# Node.net
KiCad netlist of a schematic drawn in EAGLE
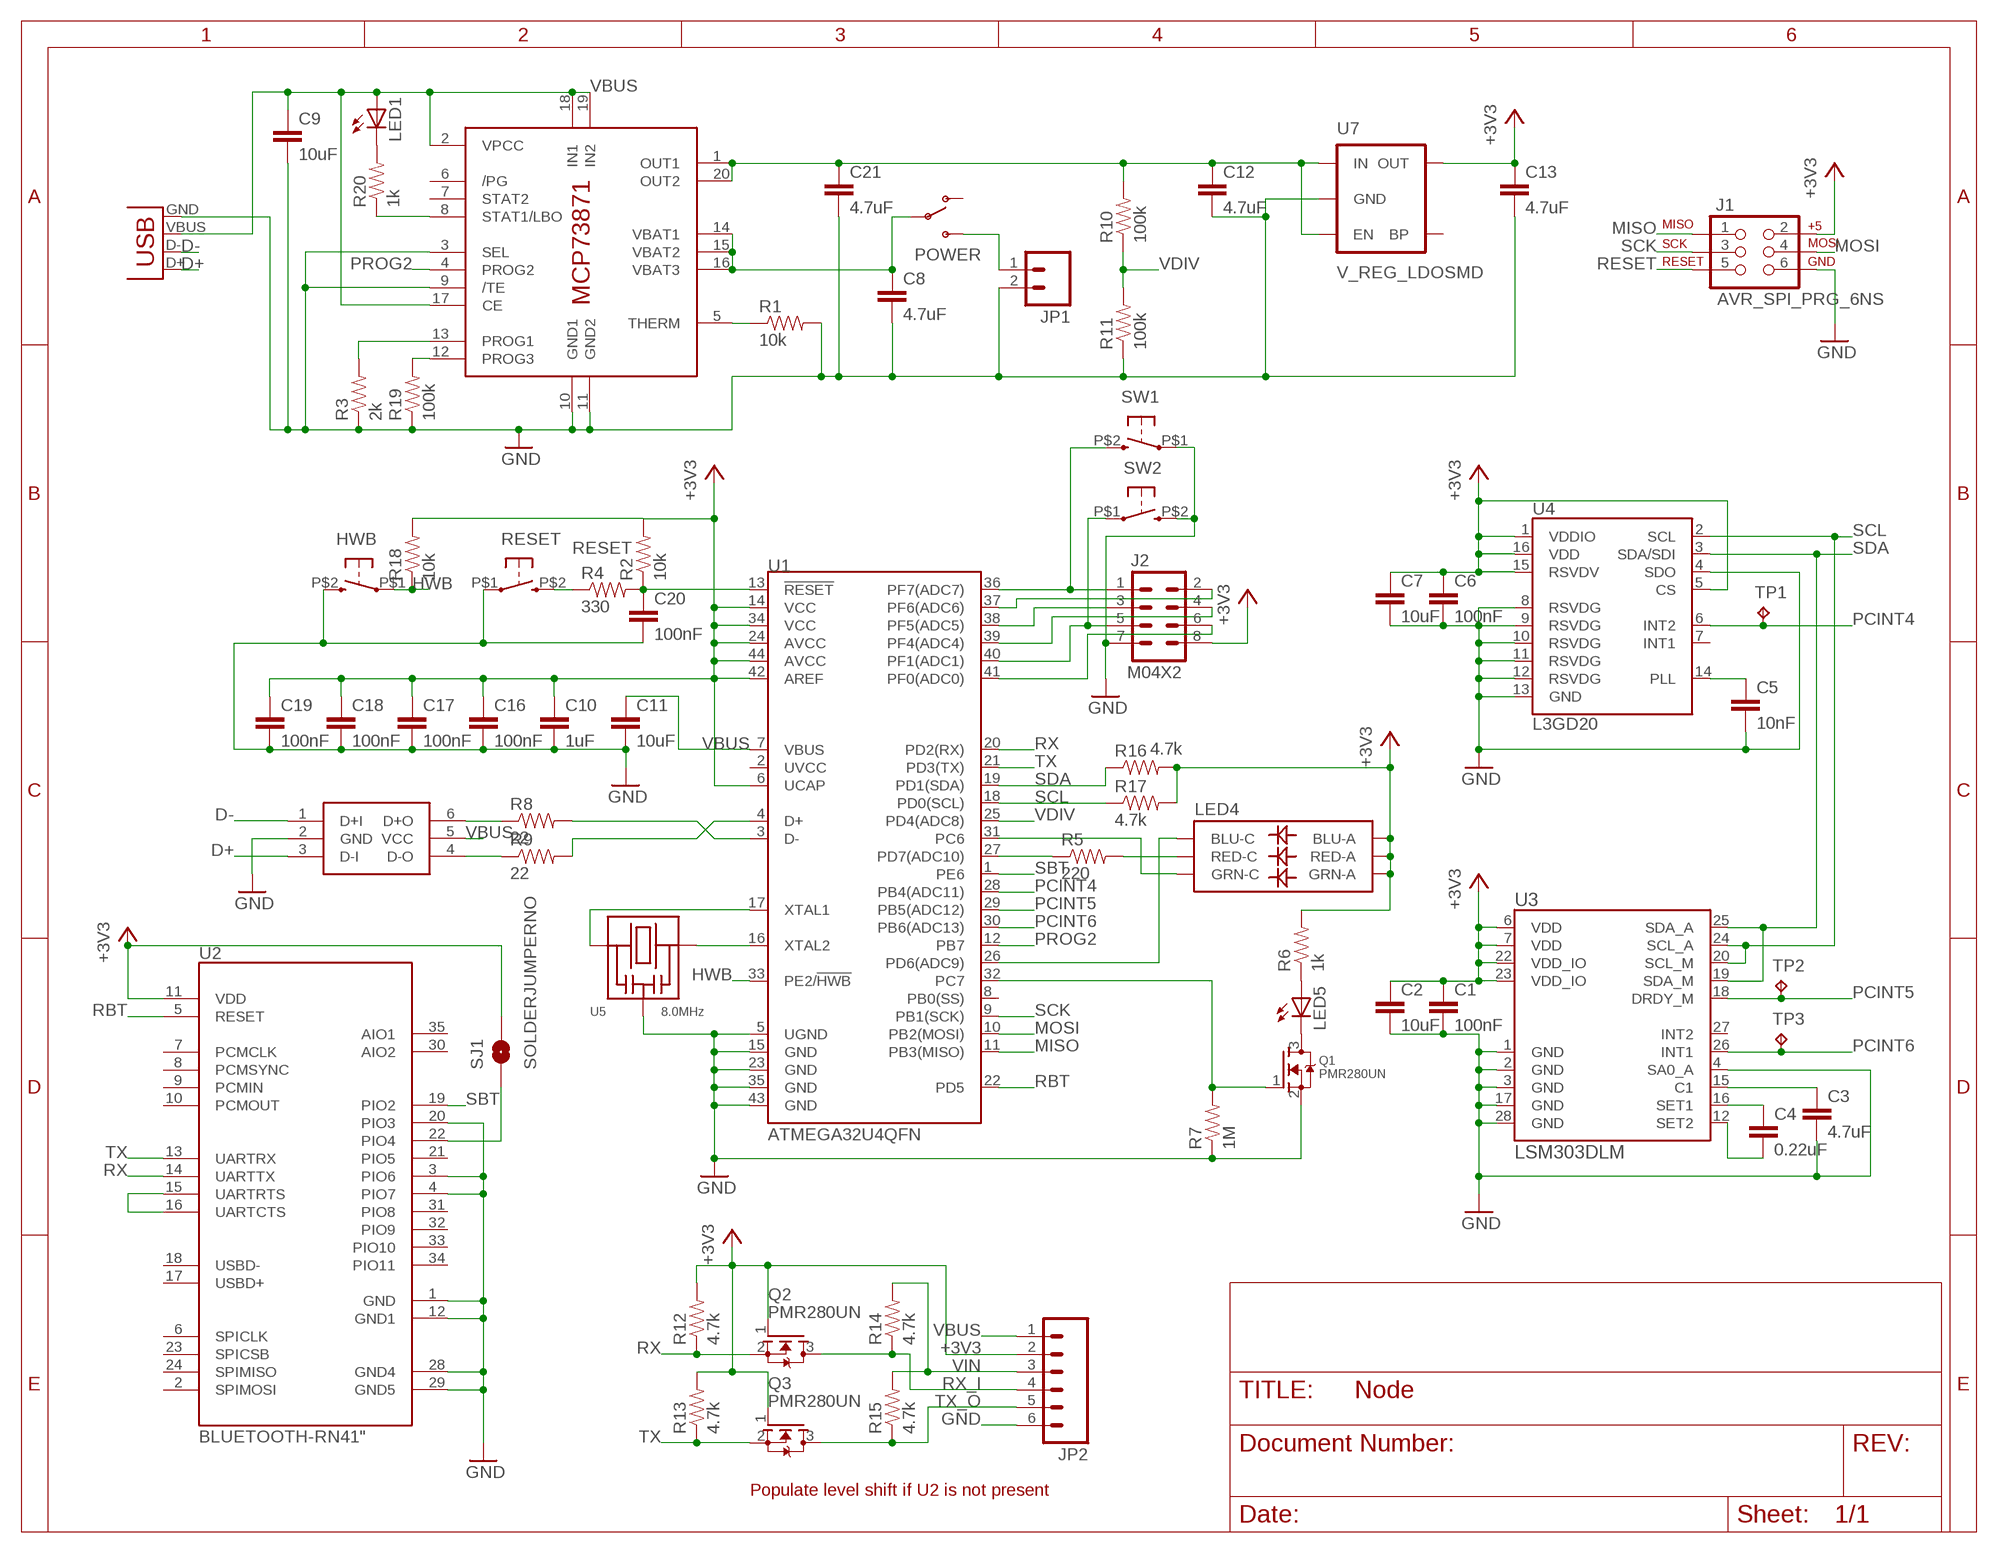
[diagram p0: schematic, sheet 1]

(export (version "E")
  (design (tool "Eeschema 10.0.6"))
  (components
    (comp (ref "C1")
      (value "100nF")
      (footprint "eagle-import:0402-CAP")
      (libsource (lib "eagle-import") (part "CAP0402-CAP"))
    )
    (comp (ref "C2")
      (value "10uF")
      (footprint "eagle-import:0603-CAP")
      (libsource (lib "eagle-import") (part "CAP0603-CAP"))
    )
    (comp (ref "C3")
      (value "4.7uF")
      (footprint "eagle-import:0603-CAP")
      (libsource (lib "eagle-import") (part "CAP0603-CAP"))
    )
    (comp (ref "C4")
      (value "0.22uF")
      (footprint "eagle-import:0402-CAP")
      (libsource (lib "eagle-import") (part "CAP0402-CAP"))
    )
    (comp (ref "C5")
      (value "10nF")
      (footprint "eagle-import:0402-CAP")
      (libsource (lib "eagle-import") (part "CAP0402-CAP"))
    )
    (comp (ref "C6")
      (value "100nF")
      (footprint "eagle-import:0402-CAP")
      (libsource (lib "eagle-import") (part "CAP0402-CAP"))
    )
    (comp (ref "C7")
      (value "10uF")
      (footprint "eagle-import:0603-CAP")
      (libsource (lib "eagle-import") (part "CAP0603-CAP"))
    )
    (comp (ref "C8")
      (value "4.7uF")
      (footprint "eagle-import:0603-CAP")
      (libsource (lib "eagle-import") (part "CAP0603-CAP"))
    )
    (comp (ref "C9")
      (value "10uF")
      (footprint "eagle-import:0603-CAP")
      (libsource (lib "eagle-import") (part "CAP0603-CAP"))
    )
    (comp (ref "C10")
      (value "1uF")
      (footprint "eagle-import:0402-CAP")
      (libsource (lib "eagle-import") (part "CAP0402-CAP"))
    )
    (comp (ref "C11")
      (value "10uF")
      (footprint "eagle-import:0603-CAP")
      (libsource (lib "eagle-import") (part "CAP0603-CAP"))
    )
    (comp (ref "C12")
      (value "4.7uF")
      (footprint "eagle-import:0603-CAP")
      (libsource (lib "eagle-import") (part "CAP0603-CAP"))
    )
    (comp (ref "C13")
      (value "4.7uF")
      (footprint "eagle-import:0603-CAP")
      (libsource (lib "eagle-import") (part "CAP0603-CAP"))
    )
    (comp (ref "C16")
      (value "100nF")
      (footprint "eagle-import:0402-CAP")
      (libsource (lib "eagle-import") (part "CAP0402-CAP"))
    )
    (comp (ref "C17")
      (value "100nF")
      (footprint "eagle-import:0402-CAP")
      (libsource (lib "eagle-import") (part "CAP0402-CAP"))
    )
    (comp (ref "C18")
      (value "100nF")
      (footprint "eagle-import:0402-CAP")
      (libsource (lib "eagle-import") (part "CAP0402-CAP"))
    )
    (comp (ref "C19")
      (value "100nF")
      (footprint "eagle-import:0402-CAP")
      (libsource (lib "eagle-import") (part "CAP0402-CAP"))
    )
    (comp (ref "C20")
      (value "100nF")
      (footprint "eagle-import:0402-CAP")
      (libsource (lib "eagle-import") (part "CAP0402-CAP"))
    )
    (comp (ref "C21")
      (value "4.7uF")
      (footprint "eagle-import:0603-CAP")
      (libsource (lib "eagle-import") (part "CAP0603-CAP"))
    )
    (comp (ref "HWB")
      (value "KSS")
      (footprint "eagle-import:KSS")
      (libsource (lib "eagle-import") (part "KSS"))
    )
    (comp (ref "J1")
      (value "AVR_SPI_PRG_6NS")
      (footprint "eagle-import:2X3-NS")
      (libsource (lib "eagle-import") (part "AVR_SPI_PRG_6NS"))
    )
    (comp (ref "J2")
      (value "M04X2")
      (footprint "eagle-import:2X4")
      (libsource (lib "eagle-import") (part "M04X2"))
    )
    (comp (ref "JP1")
      (value "M02-JST-2MM-SMT")
      (footprint "eagle-import:JST-2-SMD")
      (libsource (lib "eagle-import") (part "M02-JST-2MM-SMT"))
    )
    (comp (ref "JP2")
      (value "M06SIP")
      (footprint "eagle-import:1X06")
      (libsource (lib "eagle-import") (part "M06SIP"))
    )
    (comp (ref "LED1")
      (value "LED0603")
      (footprint "eagle-import:LED-0603")
      (libsource (lib "eagle-import") (part "LED0603"))
    )
    (comp (ref "LED4")
      (value "LED-TRICOLOR-5050LED-TRICOLOR-0606")
      (footprint "eagle-import:0606")
      (libsource (lib "eagle-import") (part "LED-TRICOLOR-5050LED-TRICOLOR-0606"))
    )
    (comp (ref "LED5")
      (value "LED0603")
      (footprint "eagle-import:LED-0603")
      (libsource (lib "eagle-import") (part "LED0603"))
    )
    (comp (ref "POWER")
      (value "SWITCH-SPST-SMD-A")
      (footprint "eagle-import:SWITCH-SPST-SMD-A")
      (libsource (lib "eagle-import") (part "SWITCH-SPST-SMD-A"))
    )
    (comp (ref "Q1")
      (value "PMR280UN")
      (footprint "eagle-import:SOT416")
      (libsource (lib "eagle-import") (part "MOSFET-N"))
    )
    (comp (ref "Q2")
      (value "PMR280UN")
      (footprint "eagle-import:SOT416")
      (libsource (lib "eagle-import") (part "MOSFET-N"))
    )
    (comp (ref "Q3")
      (value "PMR280UN")
      (footprint "eagle-import:SOT416")
      (libsource (lib "eagle-import") (part "MOSFET-N"))
    )
    (comp (ref "R1")
      (value "10k")
      (footprint "eagle-import:0402-RES")
      (libsource (lib "eagle-import") (part "RESISTOR0402-RES"))
    )
    (comp (ref "R2")
      (value "10k")
      (footprint "eagle-import:0402-RES")
      (libsource (lib "eagle-import") (part "RESISTOR0402-RES"))
    )
    (comp (ref "R3")
      (value "2k")
      (footprint "eagle-import:0402-RES")
      (libsource (lib "eagle-import") (part "RESISTOR0402-RES"))
    )
    (comp (ref "R4")
      (value "330")
      (footprint "eagle-import:0402-RES")
      (libsource (lib "eagle-import") (part "RESISTOR0402-RES"))
    )
    (comp (ref "R5")
      (value "220")
      (footprint "eagle-import:0402-RES")
      (libsource (lib "eagle-import") (part "RESISTOR0402-RES"))
    )
    (comp (ref "R6")
      (value "1k")
      (footprint "eagle-import:0402-RES")
      (libsource (lib "eagle-import") (part "RESISTOR0402-RES"))
    )
    (comp (ref "R7")
      (value "1M")
      (footprint "eagle-import:0402-RES")
      (libsource (lib "eagle-import") (part "RESISTOR0402-RES"))
    )
    (comp (ref "R8")
      (value "22")
      (footprint "eagle-import:0402-RES")
      (libsource (lib "eagle-import") (part "RESISTOR0402-RES"))
    )
    (comp (ref "R9")
      (value "22")
      (footprint "eagle-import:0402-RES")
      (libsource (lib "eagle-import") (part "RESISTOR0402-RES"))
    )
    (comp (ref "R10")
      (value "100k")
      (footprint "eagle-import:0402-RES")
      (libsource (lib "eagle-import") (part "RESISTOR0402-RES"))
    )
    (comp (ref "R11")
      (value "100k")
      (footprint "eagle-import:0402-RES")
      (libsource (lib "eagle-import") (part "RESISTOR0402-RES"))
    )
    (comp (ref "R12")
      (value "4.7k")
      (footprint "eagle-import:0402-RES")
      (libsource (lib "eagle-import") (part "RESISTOR0402-RES"))
    )
    (comp (ref "R13")
      (value "4.7k")
      (footprint "eagle-import:0402-RES")
      (libsource (lib "eagle-import") (part "RESISTOR0402-RES"))
    )
    (comp (ref "R14")
      (value "4.7k")
      (footprint "eagle-import:0402-RES")
      (libsource (lib "eagle-import") (part "RESISTOR0402-RES"))
    )
    (comp (ref "R15")
      (value "4.7k")
      (footprint "eagle-import:0402-RES")
      (libsource (lib "eagle-import") (part "RESISTOR0402-RES"))
    )
    (comp (ref "R16")
      (value "4.7k")
      (footprint "eagle-import:0402-RES")
      (libsource (lib "eagle-import") (part "RESISTOR0402-RES"))
    )
    (comp (ref "R17")
      (value "4.7k")
      (footprint "eagle-import:0402-RES")
      (libsource (lib "eagle-import") (part "RESISTOR0402-RES"))
    )
    (comp (ref "R18")
      (value "10k")
      (footprint "eagle-import:0402-RES")
      (libsource (lib "eagle-import") (part "RESISTOR0402-RES"))
    )
    (comp (ref "R19")
      (value "100k")
      (footprint "eagle-import:0402-RES")
      (libsource (lib "eagle-import") (part "RESISTOR0402-RES"))
    )
    (comp (ref "R20")
      (value "1k")
      (footprint "eagle-import:0402-RES")
      (libsource (lib "eagle-import") (part "RESISTOR0402-RES"))
    )
    (comp (ref "RESET")
      (value "KSS")
      (footprint "eagle-import:KSS")
      (libsource (lib "eagle-import") (part "KSS"))
    )
    (comp (ref "SJ1")
      (value "SOLDERJUMPERNO")
      (footprint "eagle-import:SJ_2S-NO")
      (libsource (lib "eagle-import") (part "SOLDERJUMPERNO"))
    )
    (comp (ref "SW1")
      (value "KSS")
      (footprint "eagle-import:KSS")
      (libsource (lib "eagle-import") (part "KSS"))
    )
    (comp (ref "SW2")
      (value "KSS")
      (footprint "eagle-import:KSS")
      (libsource (lib "eagle-import") (part "KSS"))
    )
    (comp (ref "TP1")
      (value "TPTP06R")
      (footprint "eagle-import:TP06R")
      (libsource (lib "eagle-import") (part "TPTP06R"))
    )
    (comp (ref "TP2")
      (value "TPTP06R")
      (footprint "eagle-import:TP06R")
      (libsource (lib "eagle-import") (part "TPTP06R"))
    )
    (comp (ref "TP3")
      (value "TPTP06R")
      (footprint "eagle-import:TP06R")
      (libsource (lib "eagle-import") (part "TPTP06R"))
    )
    (comp (ref "U1")
      (value "ATMEGA32U4QFN")
      (footprint "eagle-import:QFN-44")
      (libsource (lib "eagle-import") (part "ATMEGA32U4QFN"))
    )
    (comp (ref "U2")
      (value "BLUETOOTH-RN41\"")
      (footprint "eagle-import:RN41")
      (libsource (lib "eagle-import") (part "BLUETOOTH-RN41{dblquote}"))
    )
    (comp (ref "U3")
      (value "LSM303DLM")
      (footprint "eagle-import:LGA28-5X5")
      (libsource (lib "eagle-import") (part "LSM303DLM"))
    )
    (comp (ref "U4")
      (value "L3GD20")
      (footprint "eagle-import:LGA16-4X4")
      (libsource (lib "eagle-import") (part "L3GD20"))
    )
    (comp (ref "U5")
      (value "8.0MHz")
      (footprint "eagle-import:SMT_RESONATOR_3731")
      (libsource (lib "eagle-import") (part "RESONATOR"))
    )
    (comp (ref "U6")
      (value "MCP73871")
      (footprint "eagle-import:QFN20")
      (libsource (lib "eagle-import") (part "MCP73871"))
    )
    (comp (ref "U7")
      (value "V_REG_LDOSMD")
      (footprint "eagle-import:SOT23-5")
      (libsource (lib "eagle-import") (part "V_REG_LDOSMD"))
    )
    (comp (ref "U9")
      (value "RCLAMP0502A")
      (footprint "eagle-import:SOT-666")
      (libsource (lib "eagle-import") (part "RCLAMP0502A"))
    )
    (comp (ref "X1")
      (value "USBSMD")
      (footprint "eagle-import:USB-MINIB")
      (libsource (lib "eagle-import") (part "USBSMD"))
    )
  )
  (nets
    (net (code "1") (name "+3V3") (class "Default")
      (node (ref "C1") (pin "1") (pinfunction "1_1") (pintype "passive"))
      (node (ref "C10") (pin "1") (pinfunction "1_1") (pintype "passive"))
      (node (ref "C13") (pin "1") (pinfunction "1_1") (pintype "passive"))
      (node (ref "C16") (pin "1") (pinfunction "1_1") (pintype "passive"))
      (node (ref "C17") (pin "1") (pinfunction "1_1") (pintype "passive"))
      (node (ref "C18") (pin "1") (pinfunction "1_1") (pintype "passive"))
      (node (ref "C19") (pin "1") (pinfunction "1_1") (pintype "passive"))
      (node (ref "C2") (pin "1") (pinfunction "1_1") (pintype "passive"))
      (node (ref "C6") (pin "1") (pinfunction "1_1") (pintype "passive"))
      (node (ref "C7") (pin "1") (pinfunction "1_1") (pintype "passive"))
      (node (ref "J1") (pin "2") (pinfunction "2_2") (pintype "passive"))
      (node (ref "J2") (pin "8") (pinfunction "8_8") (pintype "passive"))
      (node (ref "JP2") (pin "2") (pinfunction "2_2") (pintype "passive"))
      (node (ref "LED4") (pin "4") (pinfunction "BLU-A_4") (pintype "bidirectional"))
      (node (ref "LED4") (pin "5") (pinfunction "RED-A_5") (pintype "bidirectional"))
      (node (ref "LED4") (pin "6") (pinfunction "GRN-A_6") (pintype "bidirectional"))
      (node (ref "Q2") (pin "1") (pinfunction "G_1") (pintype "bidirectional"))
      (node (ref "Q3") (pin "1") (pinfunction "G_1") (pintype "bidirectional"))
      (node (ref "R12") (pin "2") (pinfunction "2_2") (pintype "passive"))
      (node (ref "R13") (pin "2") (pinfunction "2_2") (pintype "passive"))
      (node (ref "R16") (pin "2") (pinfunction "2_2") (pintype "passive"))
      (node (ref "R17") (pin "2") (pinfunction "2_2") (pintype "passive"))
      (node (ref "R18") (pin "2") (pinfunction "2_2") (pintype "passive"))
      (node (ref "R2") (pin "2") (pinfunction "2_2") (pintype "passive"))
      (node (ref "R6") (pin "2") (pinfunction "2_2") (pintype "passive"))
      (node (ref "SJ1") (pin "2") (pinfunction "2_2") (pintype "passive"))
      (node (ref "U1") (pin "14") (pinfunction "VCC_14") (pintype "bidirectional"))
      (node (ref "U1") (pin "24") (pinfunction "AVCC_24") (pintype "bidirectional"))
      (node (ref "U1") (pin "34") (pinfunction "VCC_34") (pintype "bidirectional"))
      (node (ref "U1") (pin "42") (pinfunction "AREF_42") (pintype "bidirectional"))
      (node (ref "U1") (pin "44") (pinfunction "AVCC_44") (pintype "bidirectional"))
      (node (ref "U1") (pin "6") (pinfunction "UCAP_6") (pintype "bidirectional"))
      (node (ref "U2") (pin "11") (pinfunction "VDD_11") (pintype "bidirectional"))
      (node (ref "U3") (pin "22") (pinfunction "VDD_IO_22") (pintype "bidirectional"))
      (node (ref "U3") (pin "23") (pinfunction "VDD_IO_23") (pintype "bidirectional"))
      (node (ref "U3") (pin "6") (pinfunction "VDD_6") (pintype "bidirectional"))
      (node (ref "U3") (pin "7") (pinfunction "VDD_7") (pintype "bidirectional"))
      (node (ref "U4") (pin "1") (pinfunction "VDDIO_1") (pintype "bidirectional"))
      (node (ref "U4") (pin "15") (pinfunction "RSVDV_15") (pintype "bidirectional"))
      (node (ref "U4") (pin "16") (pinfunction "VDD_16") (pintype "bidirectional"))
      (node (ref "U4") (pin "5") (pinfunction "CS_5") (pintype "bidirectional"))
      (node (ref "U7") (pin "5") (pinfunction "OUT_5") (pintype "passive"))
    )
    (net (code "2") (name "/D+") (class "Default")
      (node (ref "U9") (pin "3") (pinfunction "D-I_3") (pintype "bidirectional"))
      (node (ref "X1") (pin "D+") (pinfunction "D+_D+") (pintype "bidirectional"))
    )
    (net (code "3") (name "/D-") (class "Default")
      (node (ref "U9") (pin "1") (pinfunction "D+I_1") (pintype "bidirectional"))
      (node (ref "X1") (pin "D-") (pinfunction "D-_D-") (pintype "bidirectional"))
    )
    (net (code "4") (name "/HWB") (class "Default")
      (node (ref "HWB") (pin "P$1") (pinfunction "1_P$1") (pintype "passive"))
      (node (ref "R18") (pin "1") (pinfunction "1_1") (pintype "passive"))
      (node (ref "U1") (pin "33") (pinfunction "PE2/~{HWB}_33") (pintype "bidirectional"))
    )
    (net (code "5") (name "/MISO") (class "Default")
      (node (ref "J1") (pin "1") (pinfunction "1_1") (pintype "passive"))
      (node (ref "U1") (pin "11") (pinfunction "PB3(MISO)_11") (pintype "bidirectional"))
    )
    (net (code "6") (name "/MOSI") (class "Default")
      (node (ref "J1") (pin "4") (pinfunction "4_4") (pintype "passive"))
      (node (ref "U1") (pin "10") (pinfunction "PB2(MOSI)_10") (pintype "bidirectional"))
    )
    (net (code "7") (name "/PCINT4") (class "Default")
      (node (ref "TP1") (pin "TP") (pinfunction "TP_TP") (pintype "input"))
      (node (ref "U1") (pin "28") (pinfunction "PB4(ADC11)_28") (pintype "bidirectional"))
      (node (ref "U4") (pin "6") (pinfunction "INT2_6") (pintype "bidirectional"))
    )
    (net (code "8") (name "/PCINT5") (class "Default")
      (node (ref "TP2") (pin "TP") (pinfunction "TP_TP") (pintype "input"))
      (node (ref "U1") (pin "29") (pinfunction "PB5(ADC12)_29") (pintype "bidirectional"))
      (node (ref "U3") (pin "18") (pinfunction "DRDY_M_18") (pintype "bidirectional"))
    )
    (net (code "9") (name "/PCINT6") (class "Default")
      (node (ref "TP3") (pin "TP") (pinfunction "TP_TP") (pintype "input"))
      (node (ref "U1") (pin "30") (pinfunction "PB6(ADC13)_30") (pintype "bidirectional"))
      (node (ref "U3") (pin "26") (pinfunction "INT1_26") (pintype "bidirectional"))
    )
    (net (code "10") (name "/PROG2") (class "Default")
      (node (ref "U1") (pin "12") (pinfunction "PB7_12") (pintype "bidirectional"))
      (node (ref "U6") (pin "4") (pinfunction "PROG2_4") (pintype "input"))
    )
    (net (code "11") (name "/RBT") (class "Default")
      (node (ref "U1") (pin "22") (pinfunction "PD5_22") (pintype "bidirectional"))
      (node (ref "U2") (pin "5") (pinfunction "RESET_5") (pintype "bidirectional"))
    )
    (net (code "12") (name "/RESET") (class "Default")
      (node (ref "J1") (pin "5") (pinfunction "5_5") (pintype "passive"))
      (node (ref "R4") (pin "1") (pinfunction "1_1") (pintype "passive"))
      (node (ref "RESET") (pin "P$2") (pinfunction "3_P$2") (pintype "passive"))
    )
    (net (code "13") (name "/RX") (class "Default")
      (node (ref "Q2") (pin "2") (pinfunction "S_2") (pintype "bidirectional"))
      (node (ref "R12") (pin "1") (pinfunction "1_1") (pintype "passive"))
      (node (ref "U1") (pin "20") (pinfunction "PD2(RX)_20") (pintype "bidirectional"))
      (node (ref "U2") (pin "14") (pinfunction "UARTTX_14") (pintype "bidirectional"))
    )
    (net (code "14") (name "/RX_I") (class "Default")
      (node (ref "JP2") (pin "4") (pinfunction "4_4") (pintype "passive"))
      (node (ref "Q2") (pin "3") (pinfunction "D_3") (pintype "bidirectional"))
      (node (ref "R14") (pin "1") (pinfunction "1_1") (pintype "passive"))
    )
    (net (code "15") (name "/SBT") (class "Default")
      (node (ref "U1") (pin "1") (pinfunction "PE6_1") (pintype "bidirectional"))
      (node (ref "U2") (pin "19") (pinfunction "PIO2_19") (pintype "bidirectional"))
    )
    (net (code "16") (name "/SCK") (class "Default")
      (node (ref "J1") (pin "3") (pinfunction "3_3") (pintype "passive"))
      (node (ref "U1") (pin "9") (pinfunction "PB1(SCK)_9") (pintype "bidirectional"))
    )
    (net (code "17") (name "/SCL") (class "Default")
      (node (ref "R17") (pin "1") (pinfunction "1_1") (pintype "passive"))
      (node (ref "U1") (pin "18") (pinfunction "PD0(SCL)_18") (pintype "bidirectional"))
      (node (ref "U3") (pin "20") (pinfunction "SCL_M_20") (pintype "bidirectional"))
      (node (ref "U3") (pin "24") (pinfunction "SCL_A_24") (pintype "bidirectional"))
      (node (ref "U4") (pin "2") (pinfunction "SCL_2") (pintype "bidirectional"))
    )
    (net (code "18") (name "/SDA") (class "Default")
      (node (ref "R16") (pin "1") (pinfunction "1_1") (pintype "passive"))
      (node (ref "U1") (pin "19") (pinfunction "PD1(SDA)_19") (pintype "bidirectional"))
      (node (ref "U3") (pin "19") (pinfunction "SDA_M_19") (pintype "bidirectional"))
      (node (ref "U3") (pin "25") (pinfunction "SDA_A_25") (pintype "bidirectional"))
      (node (ref "U4") (pin "3") (pinfunction "SDA/SDI_3") (pintype "bidirectional"))
    )
    (net (code "19") (name "/TX") (class "Default")
      (node (ref "Q3") (pin "2") (pinfunction "S_2") (pintype "bidirectional"))
      (node (ref "R13") (pin "1") (pinfunction "1_1") (pintype "passive"))
      (node (ref "U1") (pin "21") (pinfunction "PD3(TX)_21") (pintype "bidirectional"))
      (node (ref "U2") (pin "13") (pinfunction "UARTRX_13") (pintype "bidirectional"))
    )
    (net (code "20") (name "/TX_O") (class "Default")
      (node (ref "JP2") (pin "5") (pinfunction "5_5") (pintype "passive"))
      (node (ref "Q3") (pin "3") (pinfunction "D_3") (pintype "bidirectional"))
      (node (ref "R15") (pin "1") (pinfunction "1_1") (pintype "passive"))
    )
    (net (code "21") (name "/VBUS") (class "Default")
      (node (ref "C11") (pin "1") (pinfunction "1_1") (pintype "passive"))
      (node (ref "C9") (pin "1") (pinfunction "1_1") (pintype "passive"))
      (node (ref "JP2") (pin "1") (pinfunction "1_1") (pintype "passive"))
      (node (ref "LED1") (pin "A") (pinfunction "A_A") (pintype "passive"))
      (node (ref "U1") (pin "7") (pinfunction "VBUS_7") (pintype "bidirectional"))
      (node (ref "U6") (pin "17") (pinfunction "CE_17") (pintype "input"))
      (node (ref "U6") (pin "18") (pinfunction "IN1_18") (pintype "input"))
      (node (ref "U6") (pin "19") (pinfunction "IN2_19") (pintype "input"))
      (node (ref "U6") (pin "2") (pinfunction "VPCC_2") (pintype "input"))
      (node (ref "U9") (pin "5") (pinfunction "VCC_5") (pintype "bidirectional"))
      (node (ref "X1") (pin "VBUS") (pinfunction "VBUS_VBUS") (pintype "bidirectional"))
    )
    (net (code "22") (name "/VDIV") (class "Default")
      (node (ref "R10") (pin "1") (pinfunction "1_1") (pintype "passive"))
      (node (ref "R11") (pin "2") (pinfunction "2_2") (pintype "passive"))
      (node (ref "U1") (pin "25") (pinfunction "PD4(ADC8)_25") (pintype "bidirectional"))
    )
    (net (code "23") (name "/VIN") (class "Default")
      (node (ref "JP2") (pin "3") (pinfunction "3_3") (pintype "passive"))
      (node (ref "R14") (pin "2") (pinfunction "2_2") (pintype "passive"))
      (node (ref "R15") (pin "2") (pinfunction "2_2") (pintype "passive"))
    )
    (net (code "24") (name "GND") (class "Default")
      (node (ref "C1") (pin "2") (pinfunction "2_2") (pintype "passive"))
      (node (ref "C10") (pin "2") (pinfunction "2_2") (pintype "passive"))
      (node (ref "C11") (pin "2") (pinfunction "2_2") (pintype "passive"))
      (node (ref "C12") (pin "2") (pinfunction "2_2") (pintype "passive"))
      (node (ref "C13") (pin "2") (pinfunction "2_2") (pintype "passive"))
      (node (ref "C16") (pin "2") (pinfunction "2_2") (pintype "passive"))
      (node (ref "C17") (pin "2") (pinfunction "2_2") (pintype "passive"))
      (node (ref "C18") (pin "2") (pinfunction "2_2") (pintype "passive"))
      (node (ref "C19") (pin "2") (pinfunction "2_2") (pintype "passive"))
      (node (ref "C2") (pin "2") (pinfunction "2_2") (pintype "passive"))
      (node (ref "C20") (pin "2") (pinfunction "2_2") (pintype "passive"))
      (node (ref "C21") (pin "2") (pinfunction "2_2") (pintype "passive"))
      (node (ref "C3") (pin "2") (pinfunction "2_2") (pintype "passive"))
      (node (ref "C5") (pin "2") (pinfunction "2_2") (pintype "passive"))
      (node (ref "C6") (pin "2") (pinfunction "2_2") (pintype "passive"))
      (node (ref "C7") (pin "2") (pinfunction "2_2") (pintype "passive"))
      (node (ref "C8") (pin "2") (pinfunction "2_2") (pintype "passive"))
      (node (ref "C9") (pin "2") (pinfunction "2_2") (pintype "passive"))
      (node (ref "HWB") (pin "P$2") (pinfunction "3_P$2") (pintype "passive"))
      (node (ref "J1") (pin "6") (pinfunction "6_6") (pintype "passive"))
      (node (ref "J2") (pin "7") (pinfunction "7_7") (pintype "passive"))
      (node (ref "JP1") (pin "2") (pinfunction "2_2") (pintype "passive"))
      (node (ref "JP2") (pin "6") (pinfunction "6_6") (pintype "passive"))
      (node (ref "Q1") (pin "2") (pinfunction "S_2") (pintype "bidirectional"))
      (node (ref "R1") (pin "2") (pinfunction "2_2") (pintype "passive"))
      (node (ref "R11") (pin "1") (pinfunction "1_1") (pintype "passive"))
      (node (ref "R19") (pin "1") (pinfunction "1_1") (pintype "passive"))
      (node (ref "R3") (pin "1") (pinfunction "1_1") (pintype "passive"))
      (node (ref "R7") (pin "1") (pinfunction "1_1") (pintype "passive"))
      (node (ref "RESET") (pin "P$1") (pinfunction "1_P$1") (pintype "passive"))
      (node (ref "SW1") (pin "P$1") (pinfunction "1_P$1") (pintype "passive"))
      (node (ref "SW2") (pin "P$2") (pinfunction "3_P$2") (pintype "passive"))
      (node (ref "U1") (pin "15") (pinfunction "GND_15") (pintype "bidirectional"))
      (node (ref "U1") (pin "23") (pinfunction "GND_23") (pintype "bidirectional"))
      (node (ref "U1") (pin "35") (pinfunction "GND_35") (pintype "bidirectional"))
      (node (ref "U1") (pin "43") (pinfunction "GND_43") (pintype "bidirectional"))
      (node (ref "U1") (pin "5") (pinfunction "UGND_5") (pintype "bidirectional"))
      (node (ref "U2") (pin "1") (pinfunction "GND_1") (pintype "bidirectional"))
      (node (ref "U2") (pin "12") (pinfunction "GND1_12") (pintype "bidirectional"))
      (node (ref "U2") (pin "20") (pinfunction "PIO3_20") (pintype "bidirectional"))
      (node (ref "U2") (pin "28") (pinfunction "GND4_28") (pintype "bidirectional"))
      (node (ref "U2") (pin "29") (pinfunction "GND5_29") (pintype "bidirectional"))
      (node (ref "U2") (pin "3") (pinfunction "PIO6_3") (pintype "bidirectional"))
      (node (ref "U2") (pin "4") (pinfunction "PIO7_4") (pintype "bidirectional"))
      (node (ref "U3") (pin "1") (pinfunction "GND_1") (pintype "bidirectional"))
      (node (ref "U3") (pin "17") (pinfunction "GND_17") (pintype "bidirectional"))
      (node (ref "U3") (pin "2") (pinfunction "GND_2") (pintype "bidirectional"))
      (node (ref "U3") (pin "28") (pinfunction "GND_28") (pintype "bidirectional"))
      (node (ref "U3") (pin "3") (pinfunction "GND_3") (pintype "bidirectional"))
      (node (ref "U3") (pin "4") (pinfunction "SA0_A_4") (pintype "bidirectional"))
      (node (ref "U4") (pin "10") (pinfunction "RSVDG_10") (pintype "bidirectional"))
      (node (ref "U4") (pin "11") (pinfunction "RSVDG_11") (pintype "bidirectional"))
      (node (ref "U4") (pin "12") (pinfunction "RSVDG_12") (pintype "bidirectional"))
      (node (ref "U4") (pin "13") (pinfunction "GND_13") (pintype "bidirectional"))
      (node (ref "U4") (pin "4") (pinfunction "SDO_4") (pintype "bidirectional"))
      (node (ref "U4") (pin "8") (pinfunction "RSVDG_8") (pintype "bidirectional"))
      (node (ref "U4") (pin "9") (pinfunction "RSVDG_9") (pintype "bidirectional"))
      (node (ref "U5") (pin "P$2") (pinfunction "GND_P$2") (pintype "power_in"))
      (node (ref "U6") (pin "10") (pinfunction "GND1_10") (pintype "power_in"))
      (node (ref "U6") (pin "11") (pinfunction "GND2_11") (pintype "power_in"))
      (node (ref "U6") (pin "3") (pinfunction "SEL_3") (pintype "input"))
      (node (ref "U6") (pin "9") (pinfunction "/TE_9") (pintype "input"))
      (node (ref "U7") (pin "2") (pinfunction "GND_2") (pintype "input"))
      (node (ref "U9") (pin "2") (pinfunction "GND_2") (pintype "bidirectional"))
      (node (ref "X1") (pin "GND") (pinfunction "GND_GND") (pintype "bidirectional"))
    )
    (net (code "25") (name "Net-(LED1-PadC)") (class "Default")
      (node (ref "LED1") (pin "C") (pinfunction "C_C") (pintype "passive"))
      (node (ref "R20") (pin "2") (pinfunction "2_2") (pintype "passive"))
    )
    (net (code "26") (name "Net-(LED4-BLU-C)") (class "Default")
      (node (ref "LED4") (pin "1") (pinfunction "BLU-C_1") (pintype "bidirectional"))
      (node (ref "U1") (pin "26") (pinfunction "PD6(ADC9)_26") (pintype "bidirectional"))
    )
    (net (code "27") (name "Net-(LED4-GRN-C)") (class "Default")
      (node (ref "LED4") (pin "3") (pinfunction "GRN-C_3") (pintype "bidirectional"))
      (node (ref "U1") (pin "31") (pinfunction "PC6_31") (pintype "bidirectional"))
    )
    (net (code "28") (name "Net-(LED4-RED-C)") (class "Default")
      (node (ref "LED4") (pin "2") (pinfunction "RED-C_2") (pintype "bidirectional"))
      (node (ref "R5") (pin "2") (pinfunction "2_2") (pintype "passive"))
    )
    (net (code "29") (name "Net-(LED5-PadA)") (class "Default")
      (node (ref "LED5") (pin "A") (pinfunction "A_A") (pintype "passive"))
      (node (ref "R6") (pin "1") (pinfunction "1_1") (pintype "passive"))
    )
    (net (code "30") (name "Net-(POWER-P)") (class "Default")
      (node (ref "C8") (pin "1") (pinfunction "1_1") (pintype "passive"))
      (node (ref "POWER") (pin "2") (pinfunction "P_2") (pintype "passive"))
      (node (ref "U6") (pin "14") (pinfunction "VBAT1_14") (pintype "output"))
      (node (ref "U6") (pin "15") (pinfunction "VBAT2_15") (pintype "output"))
      (node (ref "U6") (pin "16") (pinfunction "VBAT3_16") (pintype "output"))
    )
    (net (code "31") (name "Net-(POWER-S)") (class "Default")
      (node (ref "JP1") (pin "1") (pinfunction "1_1") (pintype "passive"))
      (node (ref "POWER") (pin "3") (pinfunction "S_3") (pintype "passive"))
    )
    (net (code "32") (name "Net-(Q1-D)") (class "Default")
      (node (ref "LED5") (pin "C") (pinfunction "C_C") (pintype "passive"))
      (node (ref "Q1") (pin "3") (pinfunction "D_3") (pintype "bidirectional"))
    )
    (net (code "33") (name "Net-(Q1-G)") (class "Default")
      (node (ref "Q1") (pin "1") (pinfunction "G_1") (pintype "bidirectional"))
      (node (ref "R7") (pin "2") (pinfunction "2_2") (pintype "passive"))
      (node (ref "U1") (pin "32") (pinfunction "PC7_32") (pintype "bidirectional"))
    )
    (net (code "34") (name "Net-(SW1-3)") (class "Default")
      (node (ref "J2") (pin "1") (pinfunction "1_1") (pintype "passive"))
      (node (ref "SW1") (pin "P$2") (pinfunction "3_P$2") (pintype "passive"))
      (node (ref "U1") (pin "36") (pinfunction "PF7(ADC7)_36") (pintype "bidirectional"))
    )
    (net (code "35") (name "Net-(SW2-1)") (class "Default")
      (node (ref "J2") (pin "5") (pinfunction "5_5") (pintype "passive"))
      (node (ref "SW2") (pin "P$1") (pinfunction "1_P$1") (pintype "passive"))
      (node (ref "U1") (pin "40") (pinfunction "PF1(ADC1)_40") (pintype "bidirectional"))
    )
    (net (code "36") (name "Net-(U1-D+)") (class "Default")
      (node (ref "R9") (pin "2") (pinfunction "2_2") (pintype "passive"))
      (node (ref "U1") (pin "4") (pinfunction "D+_4") (pintype "bidirectional"))
    )
    (net (code "37") (name "Net-(U1-D-)") (class "Default")
      (node (ref "R8") (pin "2") (pinfunction "2_2") (pintype "passive"))
      (node (ref "U1") (pin "3") (pinfunction "D-_3") (pintype "bidirectional"))
    )
    (net (code "38") (name "Net-(U1-PD7(ADC10))") (class "Default")
      (node (ref "R5") (pin "1") (pinfunction "1_1") (pintype "passive"))
      (node (ref "U1") (pin "27") (pinfunction "PD7(ADC10)_27") (pintype "bidirectional"))
    )
    (net (code "39") (name "Net-(U1-PF0(ADC0))") (class "Default")
      (node (ref "J2") (pin "6") (pinfunction "6_6") (pintype "passive"))
      (node (ref "U1") (pin "41") (pinfunction "PF0(ADC0)_41") (pintype "bidirectional"))
    )
    (net (code "40") (name "Net-(U1-PF4(ADC4))") (class "Default")
      (node (ref "J2") (pin "4") (pinfunction "4_4") (pintype "passive"))
      (node (ref "U1") (pin "39") (pinfunction "PF4(ADC4)_39") (pintype "bidirectional"))
    )
    (net (code "41") (name "Net-(U1-PF5(ADC5))") (class "Default")
      (node (ref "J2") (pin "3") (pinfunction "3_3") (pintype "passive"))
      (node (ref "U1") (pin "38") (pinfunction "PF5(ADC5)_38") (pintype "bidirectional"))
    )
    (net (code "42") (name "Net-(U1-PF6(ADC6))") (class "Default")
      (node (ref "J2") (pin "2") (pinfunction "2_2") (pintype "passive"))
      (node (ref "U1") (pin "37") (pinfunction "PF6(ADC6)_37") (pintype "bidirectional"))
    )
    (net (code "43") (name "Net-(U1-XTAL1)") (class "Default")
      (node (ref "U1") (pin "17") (pinfunction "XTAL1_17") (pintype "bidirectional"))
      (node (ref "U5") (pin "P$1") (pinfunction "1_P$1") (pintype "bidirectional"))
    )
    (net (code "44") (name "Net-(U1-XTAL2)") (class "Default")
      (node (ref "U1") (pin "16") (pinfunction "XTAL2_16") (pintype "bidirectional"))
      (node (ref "U5") (pin "P$3") (pinfunction "2_P$3") (pintype "bidirectional"))
    )
    (net (code "45") (name "Net-(U1-~{RESET})") (class "Default")
      (node (ref "C20") (pin "1") (pinfunction "1_1") (pintype "passive"))
      (node (ref "R2") (pin "1") (pinfunction "1_1") (pintype "passive"))
      (node (ref "R4") (pin "2") (pinfunction "2_2") (pintype "passive"))
      (node (ref "U1") (pin "13") (pinfunction "~{RESET}_13") (pintype "bidirectional"))
    )
    (net (code "46") (name "Net-(U2-PIO4)") (class "Default")
      (node (ref "SJ1") (pin "1") (pinfunction "1_1") (pintype "passive"))
      (node (ref "U2") (pin "22") (pinfunction "PIO4_22") (pintype "bidirectional"))
    )
    (net (code "47") (name "Net-(U2-UARTCTS)") (class "Default")
      (node (ref "U2") (pin "15") (pinfunction "UARTRTS_15") (pintype "bidirectional"))
      (node (ref "U2") (pin "16") (pinfunction "UARTCTS_16") (pintype "bidirectional"))
    )
    (net (code "48") (name "Net-(U3-C1)") (class "Default")
      (node (ref "C3") (pin "1") (pinfunction "1_1") (pintype "passive"))
      (node (ref "U3") (pin "15") (pinfunction "C1_15") (pintype "bidirectional"))
    )
    (net (code "49") (name "Net-(U3-SET1)") (class "Default")
      (node (ref "C4") (pin "1") (pinfunction "1_1") (pintype "passive"))
      (node (ref "U3") (pin "16") (pinfunction "SET1_16") (pintype "bidirectional"))
    )
    (net (code "50") (name "Net-(U3-SET2)") (class "Default")
      (node (ref "C4") (pin "2") (pinfunction "2_2") (pintype "passive"))
      (node (ref "U3") (pin "12") (pinfunction "SET2_12") (pintype "bidirectional"))
    )
    (net (code "51") (name "Net-(U4-PLL)") (class "Default")
      (node (ref "C5") (pin "1") (pinfunction "1_1") (pintype "passive"))
      (node (ref "U4") (pin "14") (pinfunction "PLL_14") (pintype "bidirectional"))
    )
    (net (code "52") (name "Net-(U6-OUT1)") (class "Default")
      (node (ref "C12") (pin "1") (pinfunction "1_1") (pintype "passive"))
      (node (ref "C21") (pin "1") (pinfunction "1_1") (pintype "passive"))
      (node (ref "R10") (pin "2") (pinfunction "2_2") (pintype "passive"))
      (node (ref "U6") (pin "1") (pinfunction "OUT1_1") (pintype "output"))
      (node (ref "U6") (pin "20") (pinfunction "OUT2_20") (pintype "output"))
      (node (ref "U7") (pin "1") (pinfunction "IN_1") (pintype "input"))
      (node (ref "U7") (pin "3") (pinfunction "EN_3") (pintype "input"))
    )
    (net (code "53") (name "Net-(U6-PROG1)") (class "Default")
      (node (ref "R3") (pin "2") (pinfunction "2_2") (pintype "passive"))
      (node (ref "U6") (pin "13") (pinfunction "PROG1_13") (pintype "input"))
    )
    (net (code "54") (name "Net-(U6-PROG3)") (class "Default")
      (node (ref "R19") (pin "2") (pinfunction "2_2") (pintype "passive"))
      (node (ref "U6") (pin "12") (pinfunction "PROG3_12") (pintype "input"))
    )
    (net (code "55") (name "Net-(U6-STAT1{slash}LBO)") (class "Default")
      (node (ref "R20") (pin "1") (pinfunction "1_1") (pintype "passive"))
      (node (ref "U6") (pin "8") (pinfunction "STAT1/LBO_8") (pintype "output"))
    )
    (net (code "56") (name "Net-(U6-THERM)") (class "Default")
      (node (ref "R1") (pin "1") (pinfunction "1_1") (pintype "passive"))
      (node (ref "U6") (pin "5") (pinfunction "THERM_5") (pintype "input"))
    )
    (net (code "57") (name "Net-(U9-D+O)") (class "Default")
      (node (ref "R8") (pin "1") (pinfunction "1_1") (pintype "passive"))
      (node (ref "U9") (pin "6") (pinfunction "D+O_6") (pintype "bidirectional"))
    )
    (net (code "58") (name "Net-(U9-D-O)") (class "Default")
      (node (ref "R9") (pin "1") (pinfunction "1_1") (pintype "passive"))
      (node (ref "U9") (pin "4") (pinfunction "D-O_4") (pintype "bidirectional"))
    )
    (net (code "59") (name "unconnected-(POWER-O-Pad1)") (class "Default")
      (node (ref "POWER") (pin "1") (pinfunction "O_1") (pintype "passive"))
    )
    (net (code "60") (name "unconnected-(U1-PB0(SS)-Pad8)") (class "Default")
      (node (ref "U1") (pin "8") (pinfunction "PB0(SS)_8") (pintype "bidirectional"))
    )
    (net (code "61") (name "unconnected-(U1-UVCC-Pad2)") (class "Default")
      (node (ref "U1") (pin "2") (pinfunction "UVCC_2") (pintype "bidirectional"))
    )
    (net (code "62") (name "unconnected-(U2-AIO1-Pad35)") (class "Default")
      (node (ref "U2") (pin "35") (pinfunction "AIO1_35") (pintype "bidirectional"))
    )
    (net (code "63") (name "unconnected-(U2-AIO2-Pad30)") (class "Default")
      (node (ref "U2") (pin "30") (pinfunction "AIO2_30") (pintype "bidirectional"))
    )
    (net (code "64") (name "unconnected-(U2-PCMCLK-Pad7)") (class "Default")
      (node (ref "U2") (pin "7") (pinfunction "PCMCLK_7") (pintype "bidirectional"))
    )
    (net (code "65") (name "unconnected-(U2-PCMIN-Pad9)") (class "Default")
      (node (ref "U2") (pin "9") (pinfunction "PCMIN_9") (pintype "bidirectional"))
    )
    (net (code "66") (name "unconnected-(U2-PCMOUT-Pad10)") (class "Default")
      (node (ref "U2") (pin "10") (pinfunction "PCMOUT_10") (pintype "bidirectional"))
    )
    (net (code "67") (name "unconnected-(U2-PCMSYNC-Pad8)") (class "Default")
      (node (ref "U2") (pin "8") (pinfunction "PCMSYNC_8") (pintype "bidirectional"))
    )
    (net (code "68") (name "unconnected-(U2-PIO5-Pad21)") (class "Default")
      (node (ref "U2") (pin "21") (pinfunction "PIO5_21") (pintype "bidirectional"))
    )
    (net (code "69") (name "unconnected-(U2-PIO8-Pad31)") (class "Default")
      (node (ref "U2") (pin "31") (pinfunction "PIO8_31") (pintype "bidirectional"))
    )
    (net (code "70") (name "unconnected-(U2-PIO9-Pad32)") (class "Default")
      (node (ref "U2") (pin "32") (pinfunction "PIO9_32") (pintype "bidirectional"))
    )
    (net (code "71") (name "unconnected-(U2-PIO10-Pad33)") (class "Default")
      (node (ref "U2") (pin "33") (pinfunction "PIO10_33") (pintype "bidirectional"))
    )
    (net (code "72") (name "unconnected-(U2-PIO11-Pad34)") (class "Default")
      (node (ref "U2") (pin "34") (pinfunction "PIO11_34") (pintype "bidirectional"))
    )
    (net (code "73") (name "unconnected-(U2-SPICLK-Pad6)") (class "Default")
      (node (ref "U2") (pin "6") (pinfunction "SPICLK_6") (pintype "bidirectional"))
    )
    (net (code "74") (name "unconnected-(U2-SPICSB-Pad23)") (class "Default")
      (node (ref "U2") (pin "23") (pinfunction "SPICSB_23") (pintype "bidirectional"))
    )
    (net (code "75") (name "unconnected-(U2-SPIMISO-Pad24)") (class "Default")
      (node (ref "U2") (pin "24") (pinfunction "SPIMISO_24") (pintype "bidirectional"))
    )
    (net (code "76") (name "unconnected-(U2-SPIMOSI-Pad2)") (class "Default")
      (node (ref "U2") (pin "2") (pinfunction "SPIMOSI_2") (pintype "bidirectional"))
    )
    (net (code "77") (name "unconnected-(U2-USBD+-Pad17)") (class "Default")
      (node (ref "U2") (pin "17") (pinfunction "USBD+_17") (pintype "bidirectional"))
    )
    (net (code "78") (name "unconnected-(U2-USBD--Pad18)") (class "Default")
      (node (ref "U2") (pin "18") (pinfunction "USBD-_18") (pintype "bidirectional"))
    )
    (net (code "79") (name "unconnected-(U3-INT2-Pad27)") (class "Default")
      (node (ref "U3") (pin "27") (pinfunction "INT2_27") (pintype "bidirectional"))
    )
    (net (code "80") (name "unconnected-(U4-INT1-Pad7)") (class "Default")
      (node (ref "U4") (pin "7") (pinfunction "INT1_7") (pintype "bidirectional"))
    )
    (net (code "81") (name "unconnected-(U6-STAT2-Pad7)") (class "Default")
      (node (ref "U6") (pin "7") (pinfunction "STAT2_7") (pintype "output"))
    )
    (net (code "82") (name "unconnected-(U6-{slash}PG-Pad6)") (class "Default")
      (node (ref "U6") (pin "6") (pinfunction "/PG_6") (pintype "output"))
    )
    (net (code "83") (name "unconnected-(U7-BP-Pad4)") (class "Default")
      (node (ref "U7") (pin "4") (pinfunction "BP_4") (pintype "input"))
    )
  )
)
